# Liq_Controller.net
KiCad netlist of a schematic drawn in Altium Designer
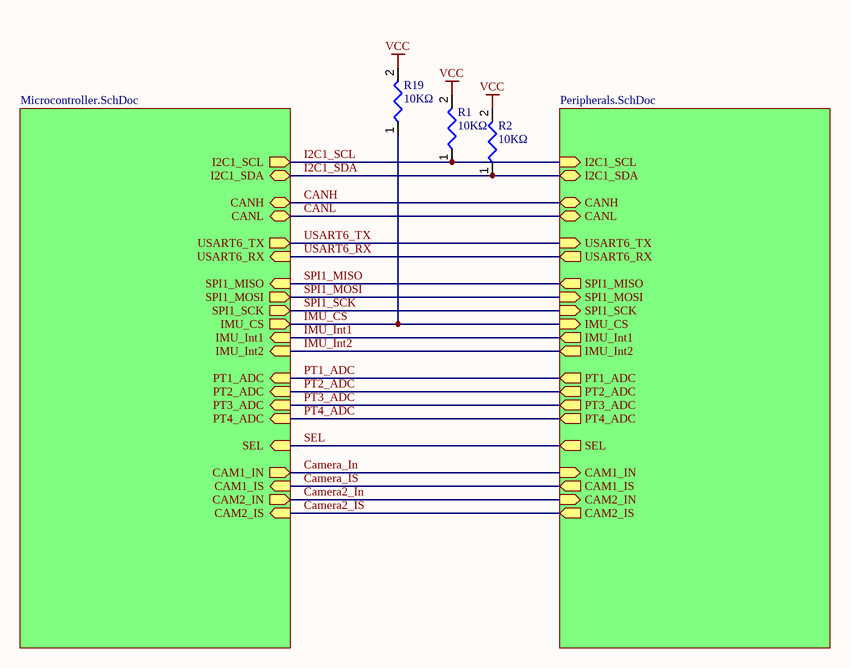
[diagram p0: Liq_Controller.SchDoc]

(export (version "E")
  (design (tool "Eeschema 10.0.6"))
  (components
    (comp (ref "R1")
      (value "10KΩ")
      (footprint "RES_0603")
      (description "Thick Film Resistors - SMD General Purpose Chip Resistor 0603, 10kOhms, 1%, 1/10W")
      (fields (field (name "TOLERANCE") "0.01") (field (name "POWER") "0.1W"))
      (libsource (lib "Resistors") (part "Resistor_BASE"))
    )
    (comp (ref "R2")
      (value "10KΩ")
      (footprint "RES_0603")
      (description "Thick Film Resistors - SMD General Purpose Chip Resistor 0603, 10kOhms, 1%, 1/10W")
      (fields (field (name "TOLERANCE") "0.01") (field (name "POWER") "0.1W"))
      (libsource (lib "Resistors") (part "Resistor_BASE"))
    )
    (comp (ref "R19")
      (value "10KΩ")
      (footprint "RES_0603")
      (description "Thick Film Resistors - SMD General Purpose Chip Resistor 0603, 10kOhms, 1%, 1/10W")
      (fields (field (name "TOLERANCE") "0.01") (field (name "POWER") "0.1W"))
      (libsource (lib "Resistors") (part "Resistor_BASE"))
    )
  )
  (nets
    (net (code "7") (name "/I2C1_SCL") (class "Default")
      (node (ref "R1") (pin "1") (pinfunction "1_1") (pintype "passive"))
    )
    (net (code "8") (name "/I2C1_SDA") (class "Default")
      (node (ref "R2") (pin "1") (pinfunction "1_1") (pintype "passive"))
    )
    (net (code "9") (name "/IMU_CS") (class "Default")
      (node (ref "R19") (pin "1") (pinfunction "1_1") (pintype "passive"))
    )
    (net (code "22") (name "VCC") (class "Default")
      (node (ref "R1") (pin "2") (pinfunction "2_2") (pintype "passive"))
      (node (ref "R19") (pin "2") (pinfunction "2_2") (pintype "passive"))
      (node (ref "R2") (pin "2") (pinfunction "2_2") (pintype "passive"))
    )
  )
)
